# BoB_Brain_v02.net
KiCad netlist of a schematic drawn in EAGLE
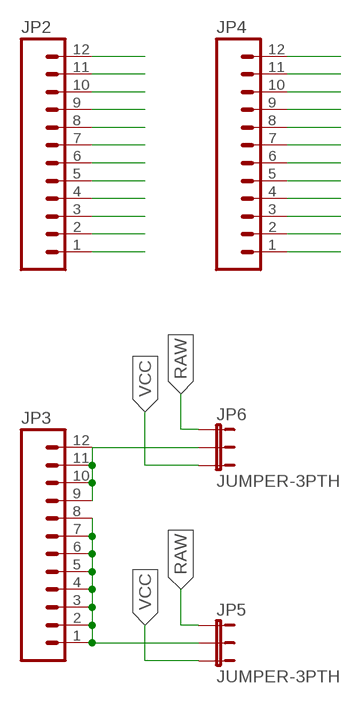
[diagram p0: schematic, sheet 1]
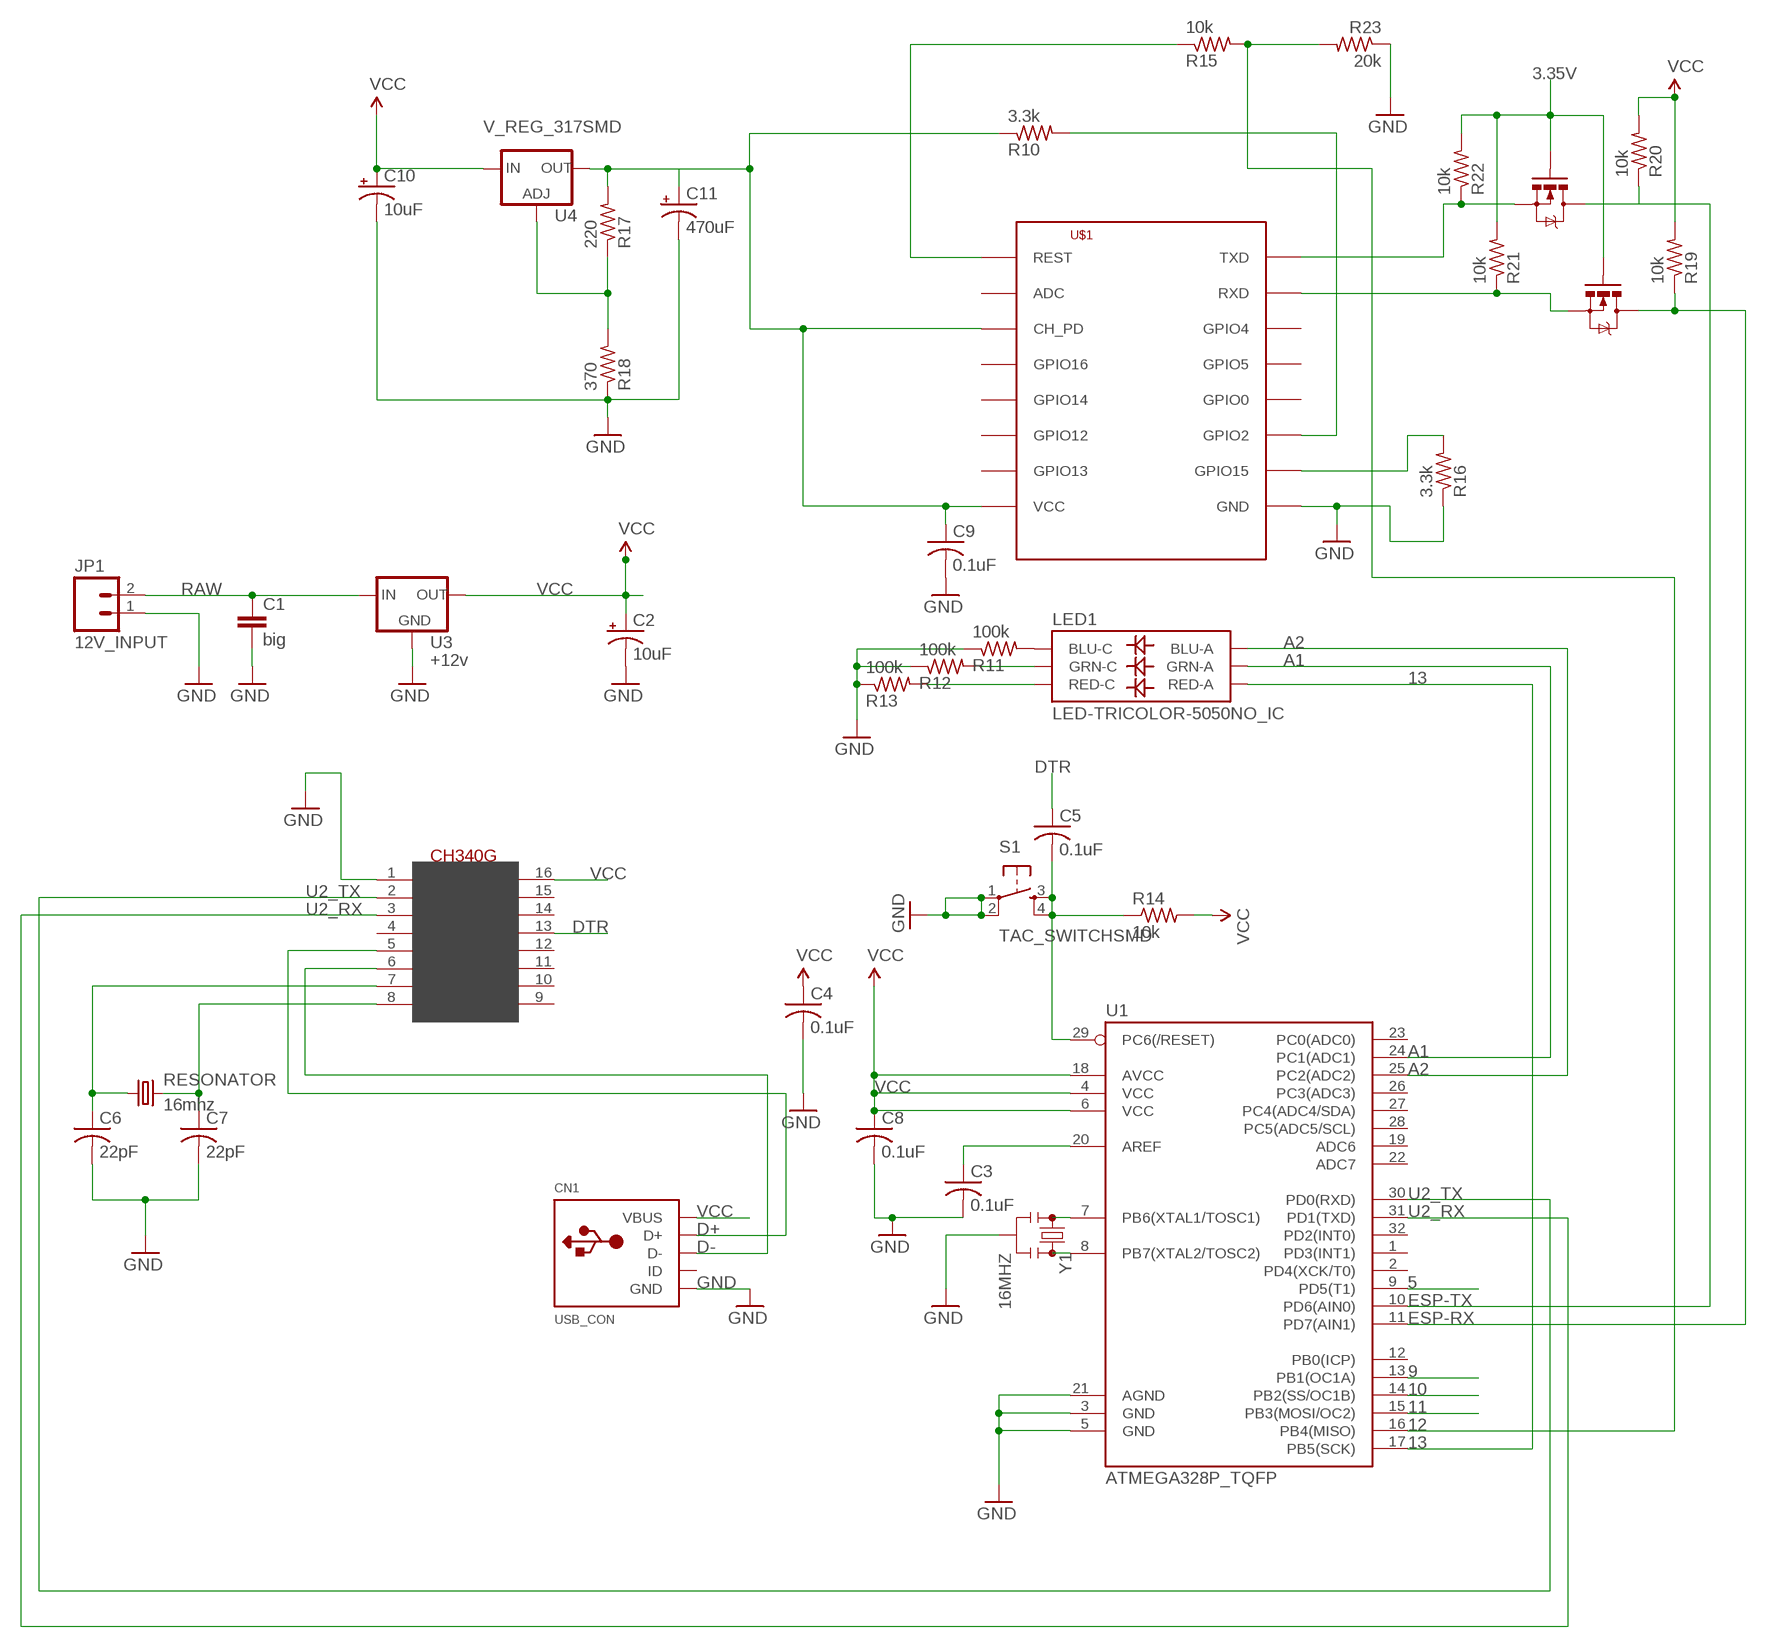
[diagram p1: schematic, sheet 2]

(export (version "E")
  (design (tool "Eeschema 10.0.6"))
  (components
    (comp (ref "JP2")
      (value "M12PTH")
      (footprint "eagle-import:1X12")
      (libsource (lib "eagle-import") (part "M12PTH"))
    )
    (comp (ref "JP3")
      (value "M12PTH")
      (footprint "eagle-import:1X12")
      (libsource (lib "eagle-import") (part "M12PTH"))
    )
    (comp (ref "JP4")
      (value "M12PTH")
      (footprint "eagle-import:1X12")
      (libsource (lib "eagle-import") (part "M12PTH"))
    )
    (comp (ref "JP5")
      (value "JUMPER-3PTH")
      (footprint "eagle-import:1X03")
      (libsource (lib "eagle-import") (part "JUMPER-3PTH"))
    )
    (comp (ref "JP6")
      (value "JUMPER-3PTH")
      (footprint "eagle-import:1X03")
      (libsource (lib "eagle-import") (part "JUMPER-3PTH"))
    )
    (comp (ref "C1")
      (value "big")
      (footprint "eagle-import:CAP-PTH-5MM")
      (libsource (lib "eagle-import") (part "CAPPTH1"))
    )
    (comp (ref "C2")
      (value "10uF")
      (footprint "eagle-import:EIA3528")
      (libsource (lib "eagle-import") (part "CAP_POL3528"))
    )
    (comp (ref "C3")
      (value "0.1uF")
      (footprint "eagle-import:C0402")
      (libsource (lib "eagle-import") (part "C-USC0402"))
    )
    (comp (ref "C4")
      (value "0.1uF")
      (footprint "eagle-import:C0805K")
      (libsource (lib "eagle-import") (part "C-USC0805K"))
    )
    (comp (ref "C5")
      (value "0.1uF")
      (footprint "eagle-import:C0805K")
      (libsource (lib "eagle-import") (part "C-USC0805K"))
    )
    (comp (ref "C6")
      (value "22pF")
      (footprint "eagle-import:C0805K")
      (libsource (lib "eagle-import") (part "C-USC0805K"))
    )
    (comp (ref "C7")
      (value "22pF")
      (footprint "eagle-import:C0805K")
      (libsource (lib "eagle-import") (part "C-USC0805K"))
    )
    (comp (ref "C8")
      (value "0.1uF")
      (footprint "eagle-import:C0402")
      (libsource (lib "eagle-import") (part "C-USC0402"))
    )
    (comp (ref "C9")
      (value "0.1uF")
      (footprint "eagle-import:C0805K")
      (libsource (lib "eagle-import") (part "C-USC0805K"))
    )
    (comp (ref "C10")
      (value "10uF")
      (footprint "eagle-import:EIA3528")
      (libsource (lib "eagle-import") (part "CAP_POL3528"))
    )
    (comp (ref "C11")
      (value "470uF")
      (footprint "eagle-import:D_7343-31W")
      (libsource (lib "eagle-import") (part "CPOL-USD/7343-31W"))
    )
    (comp (ref "CN1")
      (value "USB_CON")
      (footprint "eagle-import:USB-MINIB")
      (libsource (lib "eagle-import") (part "USBMINIB"))
    )
    (comp (ref "JP1")
      (value "12V_INPUT")
      (footprint "eagle-import:SCREWTERMINAL-5MM-2")
      (libsource (lib "eagle-import") (part "M025MM"))
    )
    (comp (ref "LED1")
      (value "LED-TRICOLOR-5050NO_IC")
      (footprint "eagle-import:LED-TRICOLOR-5050")
      (libsource (lib "eagle-import") (part "LED-TRICOLOR-5050NO_IC"))
    )
    (comp (ref "Q1")
      (value "MOSFET-NCHANNELAO3404A")
      (footprint "eagle-import:SOT23-3")
      (libsource (lib "eagle-import") (part "MOSFET-NCHANNELAO3404A"))
    )
    (comp (ref "Q9")
      (value "MOSFET-NCHANNELAO3404A")
      (footprint "eagle-import:SOT23-3")
      (libsource (lib "eagle-import") (part "MOSFET-NCHANNELAO3404A"))
    )
    (comp (ref "R10")
      (value "3.3k")
      (footprint "eagle-import:R0805W")
      (libsource (lib "eagle-import") (part "R-US_R0805W"))
    )
    (comp (ref "R11")
      (value "100k")
      (footprint "eagle-import:R0805W")
      (libsource (lib "eagle-import") (part "R-US_R0805W"))
    )
    (comp (ref "R12")
      (value "100k")
      (footprint "eagle-import:R0805W")
      (libsource (lib "eagle-import") (part "R-US_R0805W"))
    )
    (comp (ref "R13")
      (value "100k")
      (footprint "eagle-import:R0805W")
      (libsource (lib "eagle-import") (part "R-US_R0805W"))
    )
    (comp (ref "R14")
      (value "10k")
      (footprint "eagle-import:R0805W")
      (libsource (lib "eagle-import") (part "R-US_R0805W"))
    )
    (comp (ref "R15")
      (value "10k")
      (footprint "eagle-import:R0805W")
      (libsource (lib "eagle-import") (part "R-US_R0805W"))
    )
    (comp (ref "R16")
      (value "3.3k")
      (footprint "eagle-import:R0805W")
      (libsource (lib "eagle-import") (part "R-US_R0805W"))
    )
    (comp (ref "R17")
      (value "220")
      (footprint "eagle-import:R0805W")
      (libsource (lib "eagle-import") (part "R-US_R0805W"))
    )
    (comp (ref "R18")
      (value "370")
      (footprint "eagle-import:R0805W")
      (libsource (lib "eagle-import") (part "R-US_R0805W"))
    )
    (comp (ref "R19")
      (value "10k")
      (footprint "eagle-import:R0805W")
      (libsource (lib "eagle-import") (part "R-US_R0805W"))
    )
    (comp (ref "R20")
      (value "10k")
      (footprint "eagle-import:R0805W")
      (libsource (lib "eagle-import") (part "R-US_R0805W"))
    )
    (comp (ref "R21")
      (value "10k")
      (footprint "eagle-import:R0805W")
      (libsource (lib "eagle-import") (part "R-US_R0805W"))
    )
    (comp (ref "R22")
      (value "10k")
      (footprint "eagle-import:R0805W")
      (libsource (lib "eagle-import") (part "R-US_R0805W"))
    )
    (comp (ref "R23")
      (value "20k")
      (footprint "eagle-import:R0805W")
      (libsource (lib "eagle-import") (part "R-US_R0805W"))
    )
    (comp (ref "RESONATOR")
      (value "16mhz")
      (footprint "eagle-import:HC49UP")
      (libsource (lib "eagle-import") (part "CRYSTALHC49UP"))
    )
    (comp (ref "S1")
      (value "TAC_SWITCHSMD")
      (footprint "eagle-import:TACTILE-SWITCH-SMD")
      (libsource (lib "eagle-import") (part "TAC_SWITCHSMD"))
    )
    (comp (ref "U$1")
      (value "ESP8266-07")
      (footprint "eagle-import:ESP-07")
      (libsource (lib "eagle-import") (part "ESP8266-07"))
    )
    (comp (ref "U1")
      (value "ATMEGA328P_TQFP")
      (footprint "eagle-import:TQFP32-08")
      (libsource (lib "eagle-import") (part "ATMEGA328P_TQFP"))
    )
    (comp (ref "U2")
      (value "CH340G")
      (footprint "eagle-import:SOIC16")
      (libsource (lib "eagle-import") (part "CH340G"))
    )
    (comp (ref "U3")
      (value "+12v")
      (footprint "eagle-import:TO-252")
      (libsource (lib "eagle-import") (part "V_REG_78XX7812"))
    )
    (comp (ref "U4")
      (value "V_REG_317SMD")
      (footprint "eagle-import:SOT223")
      (libsource (lib "eagle-import") (part "V_REG_317SMD"))
    )
    (comp (ref "Y1")
      (value "16MHZ")
      (footprint "eagle-import:RESONATOR-SMD")
      (libsource (lib "eagle-import") (part "RESONATOR16MHZ"))
    )
  )
  (nets
    (net (code "1") (name "3.35V") (class "Default")
      (node (ref "C11") (pin "+") (pinfunction "+_+") (pintype "passive"))
      (node (ref "C9") (pin "1") (pinfunction "1_1") (pintype "passive"))
      (node (ref "Q1") (pin "1") (pinfunction "G_1") (pintype "passive"))
      (node (ref "Q9") (pin "1") (pinfunction "G_1") (pintype "passive"))
      (node (ref "R10") (pin "1") (pinfunction "1_1") (pintype "passive"))
      (node (ref "R17") (pin "2") (pinfunction "2_2") (pintype "passive"))
      (node (ref "R21") (pin "2") (pinfunction "2_2") (pintype "passive"))
      (node (ref "R22") (pin "2") (pinfunction "2_2") (pintype "passive"))
      (node (ref "U$1") (pin "CH_PD") (pinfunction "CH_PD_CH_PD") (pintype "input"))
      (node (ref "U$1") (pin "VCC") (pinfunction "VCC_VCC") (pintype "power_in"))
      (node (ref "U4") (pin "2") (pinfunction "OUT_2") (pintype "output"))
    )
    (net (code "2") (name "5") (class "Default")
      (node (ref "U1") (pin "9") (pinfunction "PD5(T1)_9") (pintype "bidirectional"))
    )
    (net (code "3") (name "9") (class "Default")
      (node (ref "U1") (pin "13") (pinfunction "PB1(OC1A)_13") (pintype "bidirectional"))
    )
    (net (code "4") (name "10") (class "Default")
      (node (ref "U1") (pin "14") (pinfunction "PB2(SS/OC1B)_14") (pintype "bidirectional"))
    )
    (net (code "5") (name "11") (class "Default")
      (node (ref "U1") (pin "15") (pinfunction "PB3(MOSI/OC2)_15") (pintype "bidirectional"))
    )
    (net (code "6") (name "12") (class "Default")
      (node (ref "R15") (pin "2") (pinfunction "2_2") (pintype "passive"))
      (node (ref "R23") (pin "2") (pinfunction "2_2") (pintype "passive"))
      (node (ref "U1") (pin "16") (pinfunction "PB4(MISO)_16") (pintype "bidirectional"))
    )
    (net (code "7") (name "13") (class "Default")
      (node (ref "LED1") (pin "2") (pinfunction "RED-A_2") (pintype "bidirectional"))
      (node (ref "U1") (pin "17") (pinfunction "PB5(SCK)_17") (pintype "bidirectional"))
    )
    (net (code "8") (name "A1") (class "Default")
      (node (ref "LED1") (pin "1") (pinfunction "GRN-A_1") (pintype "bidirectional"))
      (node (ref "U1") (pin "24") (pinfunction "PC1(ADC1)_24") (pintype "bidirectional"))
    )
    (net (code "9") (name "A2") (class "Default")
      (node (ref "LED1") (pin "3") (pinfunction "BLU-A_3") (pintype "bidirectional"))
      (node (ref "U1") (pin "25") (pinfunction "PC2(ADC2)_25") (pintype "bidirectional"))
    )
    (net (code "10") (name "D+") (class "Default")
      (node (ref "CN1") (pin "D+") (pinfunction "D+_D+") (pintype "bidirectional"))
      (node (ref "U2") (pin "5") (pinfunction "D+_5") (pintype "bidirectional"))
    )
    (net (code "11") (name "D-") (class "Default")
      (node (ref "CN1") (pin "D-") (pinfunction "D-_D-") (pintype "bidirectional"))
      (node (ref "U2") (pin "6") (pinfunction "D-_6") (pintype "bidirectional"))
    )
    (net (code "12") (name "DTR") (class "Default")
      (node (ref "C5") (pin "1") (pinfunction "1_1") (pintype "passive"))
      (node (ref "U2") (pin "13") (pinfunction "DTR_13") (pintype "bidirectional"))
    )
    (net (code "13") (name "ESP-RX") (class "Default")
      (node (ref "Q9") (pin "3") (pinfunction "D_3") (pintype "passive"))
      (node (ref "R19") (pin "1") (pinfunction "1_1") (pintype "passive"))
      (node (ref "U1") (pin "11") (pinfunction "PD7(AIN1)_11") (pintype "bidirectional"))
    )
    (net (code "14") (name "ESP-TX") (class "Default")
      (node (ref "Q1") (pin "3") (pinfunction "D_3") (pintype "passive"))
      (node (ref "R20") (pin "1") (pinfunction "1_1") (pintype "passive"))
      (node (ref "U1") (pin "10") (pinfunction "PD6(AIN0)_10") (pintype "bidirectional"))
    )
    (net (code "15") (name "GND") (class "Default")
      (node (ref "C1") (pin "2") (pinfunction "2_2") (pintype "passive"))
      (node (ref "C10") (pin "C") (pinfunction "-_C") (pintype "passive"))
      (node (ref "C11") (pin "-") (pinfunction "-_-") (pintype "passive"))
      (node (ref "C2") (pin "C") (pinfunction "-_C") (pintype "passive"))
      (node (ref "C3") (pin "2") (pinfunction "2_2") (pintype "passive"))
      (node (ref "C4") (pin "2") (pinfunction "2_2") (pintype "passive"))
      (node (ref "C6") (pin "2") (pinfunction "2_2") (pintype "passive"))
      (node (ref "C7") (pin "2") (pinfunction "2_2") (pintype "passive"))
      (node (ref "C8") (pin "2") (pinfunction "2_2") (pintype "passive"))
      (node (ref "C9") (pin "2") (pinfunction "2_2") (pintype "passive"))
      (node (ref "CN1") (pin "GND") (pinfunction "GND_GND") (pintype "power_in"))
      (node (ref "JP1") (pin "1") (pinfunction "1_1") (pintype "passive"))
      (node (ref "JP2") (pin "1") (pinfunction "1_1") (pintype "passive"))
      (node (ref "JP2") (pin "10") (pinfunction "10_10") (pintype "passive"))
      (node (ref "JP2") (pin "11") (pinfunction "11_11") (pintype "passive"))
      (node (ref "JP2") (pin "12") (pinfunction "12_12") (pintype "passive"))
      (node (ref "JP2") (pin "2") (pinfunction "2_2") (pintype "passive"))
      (node (ref "JP2") (pin "3") (pinfunction "3_3") (pintype "passive"))
      (node (ref "JP2") (pin "4") (pinfunction "4_4") (pintype "passive"))
      (node (ref "JP2") (pin "5") (pinfunction "5_5") (pintype "passive"))
      (node (ref "JP2") (pin "6") (pinfunction "6_6") (pintype "passive"))
      (node (ref "JP2") (pin "7") (pinfunction "7_7") (pintype "passive"))
      (node (ref "JP2") (pin "8") (pinfunction "8_8") (pintype "passive"))
      (node (ref "JP2") (pin "9") (pinfunction "9_9") (pintype "passive"))
      (node (ref "R11") (pin "1") (pinfunction "1_1") (pintype "passive"))
      (node (ref "R12") (pin "1") (pinfunction "1_1") (pintype "passive"))
      (node (ref "R13") (pin "1") (pinfunction "1_1") (pintype "passive"))
      (node (ref "R16") (pin "1") (pinfunction "1_1") (pintype "passive"))
      (node (ref "R18") (pin "1") (pinfunction "1_1") (pintype "passive"))
      (node (ref "R23") (pin "1") (pinfunction "1_1") (pintype "passive"))
      (node (ref "S1") (pin "1") (pinfunction "1_1") (pintype "passive"))
      (node (ref "S1") (pin "2") (pinfunction "2_2") (pintype "passive"))
      (node (ref "U$1") (pin "GND") (pinfunction "GND_GND") (pintype "power_in"))
      (node (ref "U1") (pin "21") (pinfunction "AGND_21") (pintype "bidirectional"))
      (node (ref "U1") (pin "3") (pinfunction "GND_3") (pintype "bidirectional"))
      (node (ref "U1") (pin "5") (pinfunction "GND_5") (pintype "bidirectional"))
      (node (ref "U2") (pin "1") (pinfunction "GND_1") (pintype "bidirectional"))
      (node (ref "U3") (pin "3") (pinfunction "GND_3") (pintype "input"))
      (node (ref "Y1") (pin "2") (pinfunction "2_2") (pintype "passive"))
    )
    (net (code "16") (name "Net-(JP3-Pad1)") (class "Default")
      (node (ref "JP3") (pin "1") (pinfunction "1_1") (pintype "passive"))
      (node (ref "JP3") (pin "2") (pinfunction "2_2") (pintype "passive"))
      (node (ref "JP3") (pin "3") (pinfunction "3_3") (pintype "passive"))
      (node (ref "JP3") (pin "4") (pinfunction "4_4") (pintype "passive"))
      (node (ref "JP3") (pin "5") (pinfunction "5_5") (pintype "passive"))
      (node (ref "JP3") (pin "6") (pinfunction "6_6") (pintype "passive"))
      (node (ref "JP3") (pin "7") (pinfunction "7_7") (pintype "passive"))
      (node (ref "JP3") (pin "8") (pinfunction "8_8") (pintype "passive"))
      (node (ref "JP5") (pin "2") (pinfunction "2_2") (pintype "passive"))
    )
    (net (code "17") (name "Net-(JP3-Pad10)") (class "Default")
      (node (ref "JP3") (pin "10") (pinfunction "10_10") (pintype "passive"))
      (node (ref "JP3") (pin "11") (pinfunction "11_11") (pintype "passive"))
      (node (ref "JP3") (pin "12") (pinfunction "12_12") (pintype "passive"))
      (node (ref "JP3") (pin "9") (pinfunction "9_9") (pintype "passive"))
      (node (ref "JP6") (pin "2") (pinfunction "2_2") (pintype "passive"))
    )
    (net (code "18") (name "Net-(LED1-BLU-C)") (class "Default")
      (node (ref "LED1") (pin "4") (pinfunction "BLU-C_4") (pintype "bidirectional"))
      (node (ref "R11") (pin "2") (pinfunction "2_2") (pintype "passive"))
    )
    (net (code "19") (name "Net-(LED1-GRN-C)") (class "Default")
      (node (ref "LED1") (pin "6") (pinfunction "GRN-C_6") (pintype "bidirectional"))
      (node (ref "R12") (pin "2") (pinfunction "2_2") (pintype "passive"))
    )
    (net (code "20") (name "Net-(LED1-RED-C)") (class "Default")
      (node (ref "LED1") (pin "5") (pinfunction "RED-C_5") (pintype "bidirectional"))
      (node (ref "R13") (pin "2") (pinfunction "2_2") (pintype "passive"))
    )
    (net (code "21") (name "Net-(Q1-S)") (class "Default")
      (node (ref "Q1") (pin "2") (pinfunction "S_2") (pintype "passive"))
      (node (ref "R22") (pin "1") (pinfunction "1_1") (pintype "passive"))
      (node (ref "U$1") (pin "TXD") (pinfunction "TXD_TXD") (pintype "output"))
    )
    (net (code "22") (name "Net-(Q9-S)") (class "Default")
      (node (ref "Q9") (pin "2") (pinfunction "S_2") (pintype "passive"))
      (node (ref "R21") (pin "1") (pinfunction "1_1") (pintype "passive"))
      (node (ref "U$1") (pin "RXD") (pinfunction "RXD_RXD") (pintype "input"))
    )
    (net (code "23") (name "Net-(R10-Pad2)") (class "Default")
      (node (ref "R10") (pin "2") (pinfunction "2_2") (pintype "passive"))
      (node (ref "U$1") (pin "GPIO2") (pinfunction "GPIO2_GPIO2") (pintype "bidirectional"))
    )
    (net (code "24") (name "Net-(R15-Pad1)") (class "Default")
      (node (ref "R15") (pin "1") (pinfunction "1_1") (pintype "passive"))
      (node (ref "U$1") (pin "REST") (pinfunction "REST_REST") (pintype "bidirectional"))
    )
    (net (code "25") (name "Net-(R16-Pad2)") (class "Default")
      (node (ref "R16") (pin "2") (pinfunction "2_2") (pintype "passive"))
      (node (ref "U$1") (pin "GPIO15") (pinfunction "GPIO15_GPIO15") (pintype "input"))
    )
    (net (code "26") (name "Net-(U1-AREF)") (class "Default")
      (node (ref "C3") (pin "1") (pinfunction "1_1") (pintype "passive"))
      (node (ref "U1") (pin "20") (pinfunction "AREF_20") (pintype "bidirectional"))
    )
    (net (code "27") (name "Net-(U1-PB6(XTAL1{slash}TOSC1))") (class "Default")
      (node (ref "U1") (pin "7") (pinfunction "PB6(XTAL1/TOSC1)_7") (pintype "bidirectional"))
      (node (ref "Y1") (pin "1") (pinfunction "1_1") (pintype "passive"))
    )
    (net (code "28") (name "Net-(U1-PB7(XTAL2{slash}TOSC2))") (class "Default")
      (node (ref "U1") (pin "8") (pinfunction "PB7(XTAL2/TOSC2)_8") (pintype "bidirectional"))
      (node (ref "Y1") (pin "3") (pinfunction "3_3") (pintype "passive"))
    )
    (net (code "29") (name "Net-(U1-PC6({slash}RESET))") (class "Default")
      (node (ref "C5") (pin "2") (pinfunction "2_2") (pintype "passive"))
      (node (ref "R14") (pin "1") (pinfunction "1_1") (pintype "passive"))
      (node (ref "S1") (pin "3") (pinfunction "3_3") (pintype "passive"))
      (node (ref "S1") (pin "4") (pinfunction "4_4") (pintype "passive"))
      (node (ref "U1") (pin "29") (pinfunction "PC6(/RESET)_29") (pintype "bidirectional"))
    )
    (net (code "30") (name "Net-(U2-XI)") (class "Default")
      (node (ref "C6") (pin "1") (pinfunction "1_1") (pintype "passive"))
      (node (ref "RESONATOR") (pin "1") (pinfunction "1_1") (pintype "passive"))
      (node (ref "U2") (pin "7") (pinfunction "XI_7") (pintype "bidirectional"))
    )
    (net (code "31") (name "Net-(U2-XO)") (class "Default")
      (node (ref "C7") (pin "1") (pinfunction "1_1") (pintype "passive"))
      (node (ref "RESONATOR") (pin "2") (pinfunction "2_2") (pintype "passive"))
      (node (ref "U2") (pin "8") (pinfunction "XO_8") (pintype "bidirectional"))
    )
    (net (code "32") (name "Net-(U4-ADJ)") (class "Default")
      (node (ref "R17") (pin "1") (pinfunction "1_1") (pintype "passive"))
      (node (ref "R18") (pin "2") (pinfunction "2_2") (pintype "passive"))
      (node (ref "U4") (pin "1") (pinfunction "ADJ_1") (pintype "input"))
    )
    (net (code "33") (name "RAW") (class "Default")
      (node (ref "C1") (pin "1") (pinfunction "1_1") (pintype "passive"))
      (node (ref "JP1") (pin "2") (pinfunction "2_2") (pintype "passive"))
      (node (ref "JP5") (pin "1") (pinfunction "1_1") (pintype "passive"))
      (node (ref "JP6") (pin "1") (pinfunction "1_1") (pintype "passive"))
      (node (ref "U3") (pin "1") (pinfunction "IN_1") (pintype "input"))
    )
    (net (code "34") (name "U2_RX") (class "Default")
      (node (ref "U1") (pin "31") (pinfunction "PD1(TXD)_31") (pintype "bidirectional"))
      (node (ref "U2") (pin "3") (pinfunction "RX_3") (pintype "bidirectional"))
    )
    (net (code "35") (name "U2_TX") (class "Default")
      (node (ref "U1") (pin "30") (pinfunction "PD0(RXD)_30") (pintype "bidirectional"))
      (node (ref "U2") (pin "2") (pinfunction "TX_2") (pintype "bidirectional"))
    )
    (net (code "36") (name "VCC") (class "Default")
      (node (ref "C10") (pin "A") (pinfunction "+_A") (pintype "passive"))
      (node (ref "C2") (pin "A") (pinfunction "+_A") (pintype "passive"))
      (node (ref "C4") (pin "1") (pinfunction "1_1") (pintype "passive"))
      (node (ref "C8") (pin "1") (pinfunction "1_1") (pintype "passive"))
      (node (ref "CN1") (pin "VBUS") (pinfunction "VBUS_VBUS") (pintype "power_in"))
      (node (ref "JP5") (pin "3") (pinfunction "3_3") (pintype "passive"))
      (node (ref "JP6") (pin "3") (pinfunction "3_3") (pintype "passive"))
      (node (ref "R14") (pin "2") (pinfunction "2_2") (pintype "passive"))
      (node (ref "R19") (pin "2") (pinfunction "2_2") (pintype "passive"))
      (node (ref "R20") (pin "2") (pinfunction "2_2") (pintype "passive"))
      (node (ref "U1") (pin "18") (pinfunction "AVCC_18") (pintype "bidirectional"))
      (node (ref "U1") (pin "4") (pinfunction "VCC_4") (pintype "bidirectional"))
      (node (ref "U1") (pin "6") (pinfunction "VCC_6") (pintype "bidirectional"))
      (node (ref "U2") (pin "16") (pinfunction "VCC_16") (pintype "bidirectional"))
      (node (ref "U3") (pin "2") (pinfunction "OUT_2") (pintype "passive"))
      (node (ref "U4") (pin "3") (pinfunction "IN_3") (pintype "input"))
    )
    (net (code "37") (name "unconnected-(CN1-PadID)") (class "Default")
      (node (ref "CN1") (pin "ID") (pinfunction "ID_ID") (pintype "bidirectional"))
    )
    (net (code "38") (name "unconnected-(JP4-Pad1)") (class "Default")
      (node (ref "JP4") (pin "1") (pinfunction "1_1") (pintype "passive"))
    )
    (net (code "39") (name "unconnected-(JP4-Pad2)") (class "Default")
      (node (ref "JP4") (pin "2") (pinfunction "2_2") (pintype "passive"))
    )
    (net (code "40") (name "unconnected-(JP4-Pad3)") (class "Default")
      (node (ref "JP4") (pin "3") (pinfunction "3_3") (pintype "passive"))
    )
    (net (code "41") (name "unconnected-(JP4-Pad4)") (class "Default")
      (node (ref "JP4") (pin "4") (pinfunction "4_4") (pintype "passive"))
    )
    (net (code "42") (name "unconnected-(JP4-Pad5)") (class "Default")
      (node (ref "JP4") (pin "5") (pinfunction "5_5") (pintype "passive"))
    )
    (net (code "43") (name "unconnected-(JP4-Pad6)") (class "Default")
      (node (ref "JP4") (pin "6") (pinfunction "6_6") (pintype "passive"))
    )
    (net (code "44") (name "unconnected-(JP4-Pad7)") (class "Default")
      (node (ref "JP4") (pin "7") (pinfunction "7_7") (pintype "passive"))
    )
    (net (code "45") (name "unconnected-(JP4-Pad8)") (class "Default")
      (node (ref "JP4") (pin "8") (pinfunction "8_8") (pintype "passive"))
    )
    (net (code "46") (name "unconnected-(JP4-Pad9)") (class "Default")
      (node (ref "JP4") (pin "9") (pinfunction "9_9") (pintype "passive"))
    )
    (net (code "47") (name "unconnected-(JP4-Pad10)") (class "Default")
      (node (ref "JP4") (pin "10") (pinfunction "10_10") (pintype "passive"))
    )
    (net (code "48") (name "unconnected-(JP4-Pad11)") (class "Default")
      (node (ref "JP4") (pin "11") (pinfunction "11_11") (pintype "passive"))
    )
    (net (code "49") (name "unconnected-(JP4-Pad12)") (class "Default")
      (node (ref "JP4") (pin "12") (pinfunction "12_12") (pintype "passive"))
    )
    (net (code "50") (name "unconnected-(U$1-PadADC)") (class "Default")
      (node (ref "U$1") (pin "ADC") (pinfunction "ADC_ADC") (pintype "bidirectional"))
    )
    (net (code "51") (name "unconnected-(U$1-PadGPIO0)") (class "Default")
      (node (ref "U$1") (pin "GPIO0") (pinfunction "GPIO0_GPIO0") (pintype "bidirectional"))
    )
    (net (code "52") (name "unconnected-(U$1-PadGPIO4)") (class "Default")
      (node (ref "U$1") (pin "GPIO4") (pinfunction "GPIO4_GPIO4") (pintype "bidirectional"))
    )
    (net (code "53") (name "unconnected-(U$1-PadGPIO5)") (class "Default")
      (node (ref "U$1") (pin "GPIO5") (pinfunction "GPIO5_GPIO5") (pintype "bidirectional"))
    )
    (net (code "54") (name "unconnected-(U$1-PadGPIO12)") (class "Default")
      (node (ref "U$1") (pin "GPIO12") (pinfunction "GPIO12_GPIO12") (pintype "bidirectional"))
    )
    (net (code "55") (name "unconnected-(U$1-PadGPIO13)") (class "Default")
      (node (ref "U$1") (pin "GPIO13") (pinfunction "GPIO13_GPIO13") (pintype "bidirectional"))
    )
    (net (code "56") (name "unconnected-(U$1-PadGPIO14)") (class "Default")
      (node (ref "U$1") (pin "GPIO14") (pinfunction "GPIO14_GPIO14") (pintype "bidirectional"))
    )
    (net (code "57") (name "unconnected-(U$1-PadGPIO16)") (class "Default")
      (node (ref "U$1") (pin "GPIO16") (pinfunction "GPIO16_GPIO16") (pintype "bidirectional"))
    )
    (net (code "58") (name "unconnected-(U1-ADC6-Pad19)") (class "Default")
      (node (ref "U1") (pin "19") (pinfunction "ADC6_19") (pintype "bidirectional"))
    )
    (net (code "59") (name "unconnected-(U1-ADC7-Pad22)") (class "Default")
      (node (ref "U1") (pin "22") (pinfunction "ADC7_22") (pintype "bidirectional"))
    )
    (net (code "60") (name "unconnected-(U1-PB0(ICP)-Pad12)") (class "Default")
      (node (ref "U1") (pin "12") (pinfunction "PB0(ICP)_12") (pintype "bidirectional"))
    )
    (net (code "61") (name "unconnected-(U1-PC0(ADC0)-Pad23)") (class "Default")
      (node (ref "U1") (pin "23") (pinfunction "PC0(ADC0)_23") (pintype "bidirectional"))
    )
    (net (code "62") (name "unconnected-(U1-PC3(ADC3)-Pad26)") (class "Default")
      (node (ref "U1") (pin "26") (pinfunction "PC3(ADC3)_26") (pintype "bidirectional"))
    )
    (net (code "63") (name "unconnected-(U1-PC4(ADC4{slash}SDA)-Pad27)") (class "Default")
      (node (ref "U1") (pin "27") (pinfunction "PC4(ADC4/SDA)_27") (pintype "bidirectional"))
    )
    (net (code "64") (name "unconnected-(U1-PC5(ADC5{slash}SCL)-Pad28)") (class "Default")
      (node (ref "U1") (pin "28") (pinfunction "PC5(ADC5/SCL)_28") (pintype "bidirectional"))
    )
    (net (code "65") (name "unconnected-(U1-PD2(INT0)-Pad32)") (class "Default")
      (node (ref "U1") (pin "32") (pinfunction "PD2(INT0)_32") (pintype "bidirectional"))
    )
    (net (code "66") (name "unconnected-(U1-PD3(INT1)-Pad1)") (class "Default")
      (node (ref "U1") (pin "1") (pinfunction "PD3(INT1)_1") (pintype "bidirectional"))
    )
    (net (code "67") (name "unconnected-(U1-PD4(XCK{slash}T0)-Pad2)") (class "Default")
      (node (ref "U1") (pin "2") (pinfunction "PD4(XCK/T0)_2") (pintype "bidirectional"))
    )
    (net (code "68") (name "unconnected-(U2-CTS-Pad9)") (class "Default")
      (node (ref "U2") (pin "9") (pinfunction "CTS_9") (pintype "bidirectional"))
    )
    (net (code "69") (name "unconnected-(U2-DCD-Pad12)") (class "Default")
      (node (ref "U2") (pin "12") (pinfunction "DCD_12") (pintype "bidirectional"))
    )
    (net (code "70") (name "unconnected-(U2-DSR-Pad10)") (class "Default")
      (node (ref "U2") (pin "10") (pinfunction "DSR_10") (pintype "bidirectional"))
    )
    (net (code "71") (name "unconnected-(U2-RI-Pad11)") (class "Default")
      (node (ref "U2") (pin "11") (pinfunction "RI_11") (pintype "bidirectional"))
    )
    (net (code "72") (name "unconnected-(U2-RS232-Pad15)") (class "Default")
      (node (ref "U2") (pin "15") (pinfunction "RS232_15") (pintype "bidirectional"))
    )
    (net (code "73") (name "unconnected-(U2-RTS-Pad14)") (class "Default")
      (node (ref "U2") (pin "14") (pinfunction "RTS_14") (pintype "bidirectional"))
    )
    (net (code "74") (name "unconnected-(U2-V3-Pad4)") (class "Default")
      (node (ref "U2") (pin "4") (pinfunction "V3_4") (pintype "bidirectional"))
    )
  )
)
